# Floyd-V2-Sch.net
KiCad netlist of a schematic drawn in Altium Designer
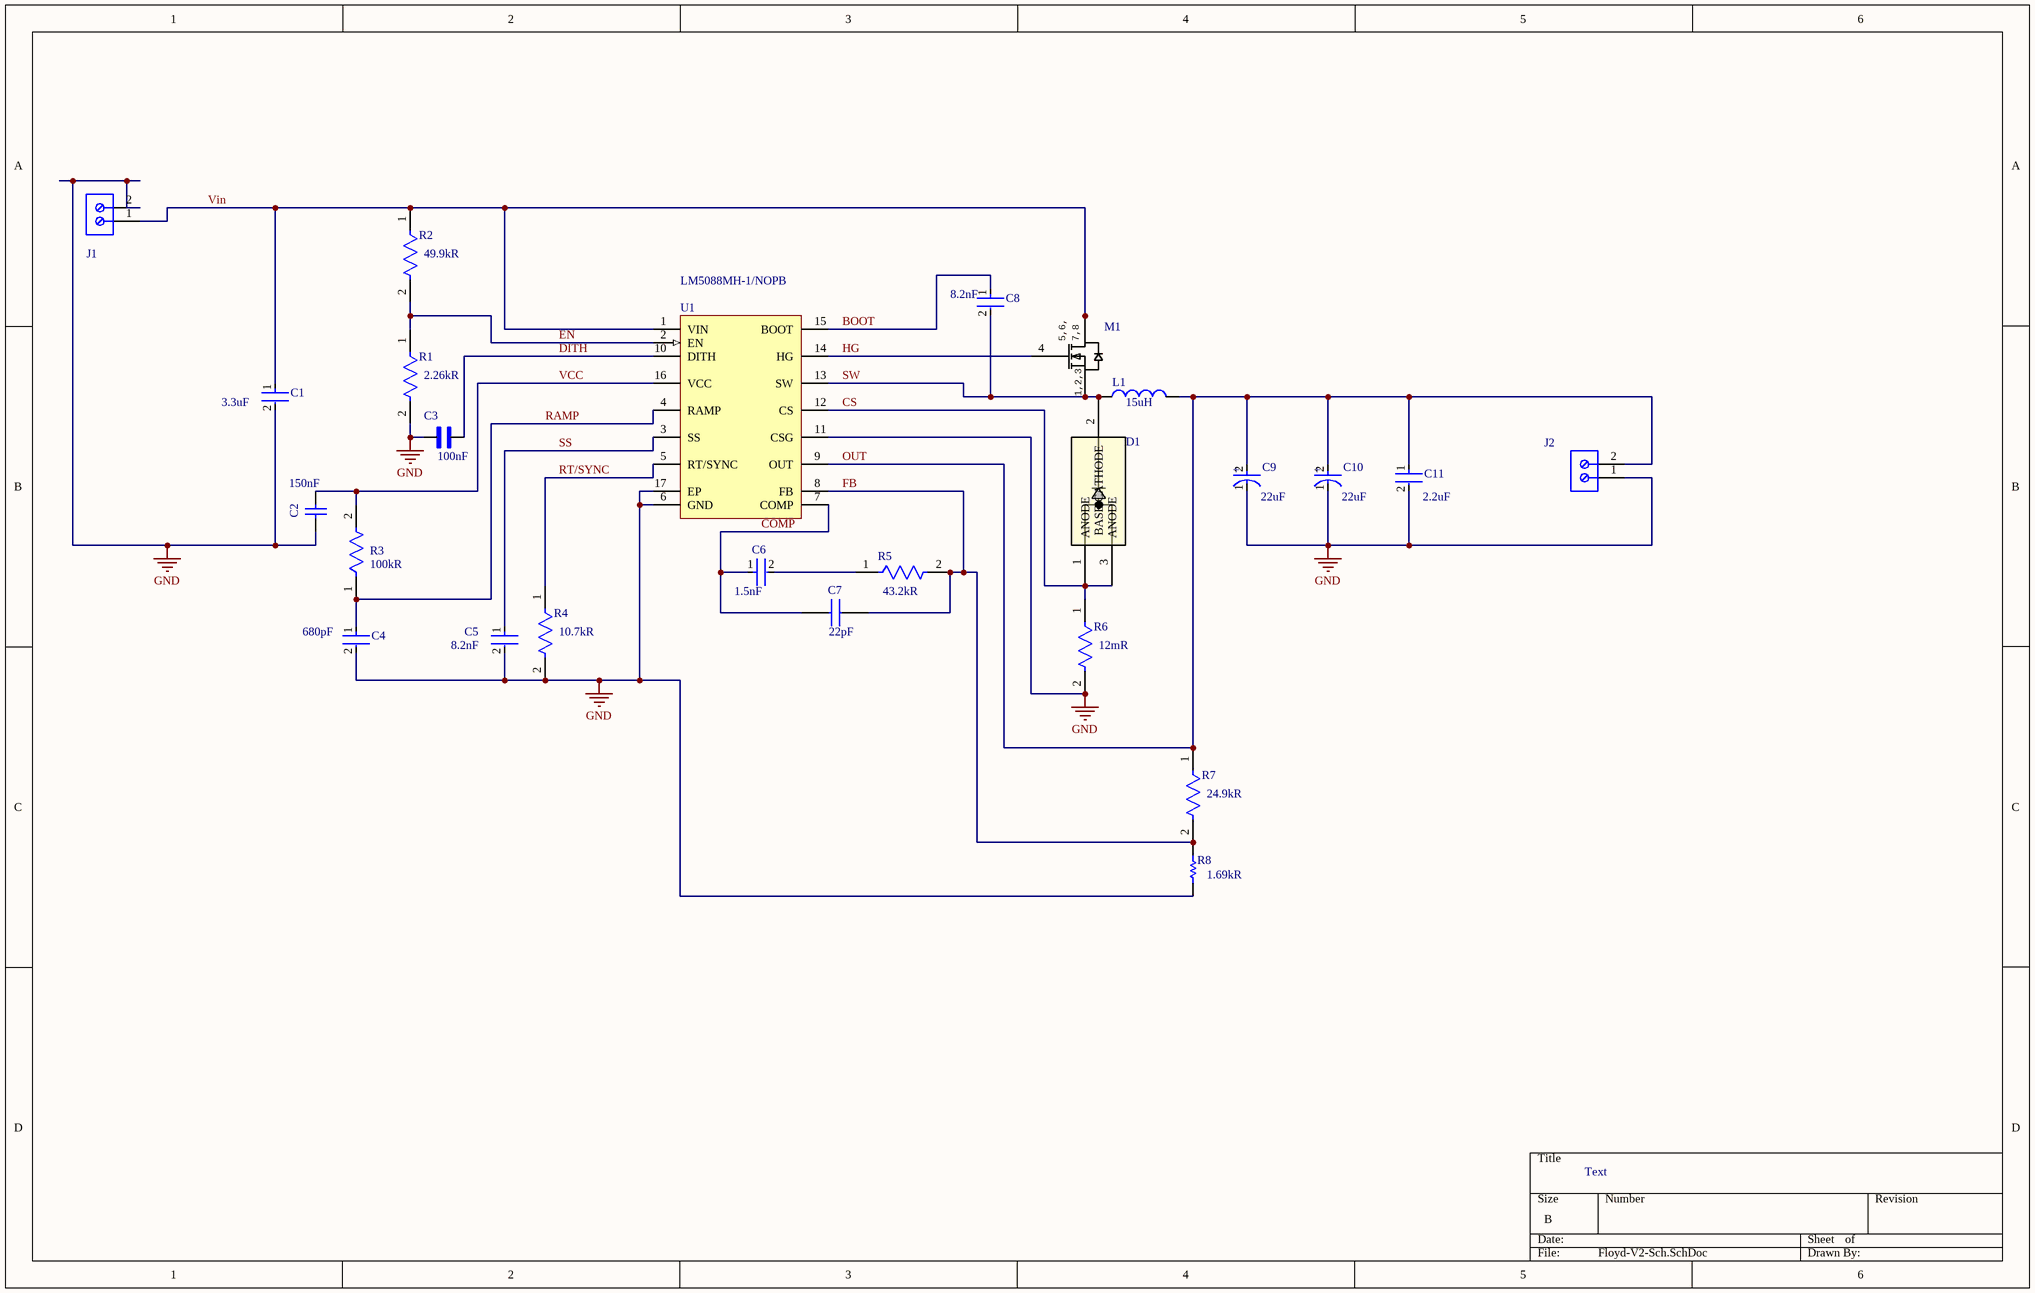
[diagram p0: Floyd-V2-Sch.SchDoc]

(export (version "E")
  (design (tool "Eeschema 10.0.6"))
  (components
    (comp (ref "C1")
      (value "C3225X7S2A335K200AB")
      (footprint "FP-C3225-200-0_4-IPC_A")
      (description "Multilayer Ceramic Capacitors 3.3uF ±10% 100V X7S SMD 1210")
      (fields (field (name "TOLERANCE") "10%") (field (name "CAPACITANCE") "3.3uF"))
      (libsource (lib "Altium Content Vault") (part "b4654b650e69147ec39a6b967a45e02"))
    )
    (comp (ref "C2")
      (value "08053C154KAT2A")
      (footprint "CAPC2013X140X50LL20T25")
      (fields (field (name "MANUFACTURER") "AVX Interconnect / Elco") (field (name "PARAMETER 1") "150nF"))
      (libsource (lib "Altium Content Vault") (part "CAP"))
    )
    (comp (ref "C3")
      (value "100nF")
      (footprint "CAPC2012X94N")
      (description "0.1 ÂµF Â±5% 25V Ceramic Capacitor X7R 0805 (2012 Metric)")
      (fields (field (name "MF") "AVX") (field (name "MP") "08053C104JAZ2A"))
      (libsource (lib "LoganIntegratedLibrary") (part "08053C104JAZ2A"))
    )
    (comp (ref "C4")
      (value "CC0805JRNPO9BN681")
      (footprint "FP-CC0805-0_1-0_7-MFG")
      (description "CAP CER 680PF 50V C0G/NPO 0805")
      (fields
        (field (name "TOLERANCE") "5%")
        (field (name "CAPACITANCE") "680pF")
        (field (name "VOLTAGE") "50V")
      )
      (libsource (lib "Altium Content Vault") (part "b4654b650e69147ec39a6b967a45e02"))
    )
    (comp (ref "C5")
      (value "CGA4C2C0G1H822J060AA")
      (footprint "FP-CGA4J-IPC_A")
      (description "Cap Ceramic 8.2nF 50V C0G 5% Pad SMD 0805 +125°C Automotive T/R")
      (fields (field (name "CAPACITANCE") "8.2nF") (field (name "TOLERANCE") "5%"))
      (libsource (lib "Altium Content Vault") (part "b4654b650e69147ec39a6b967a45e02"))
    )
    (comp (ref "C6")
      (value "C0603C152K5RACTU")
      (footprint "FP-C0603C-CF-MFG")
      (description "CAP CER 1500PF 50V X7R 0603")
      (fields
        (field (name "CAPACITANCE") "1.5nF")
        (field (name "TOLERANCE") "0.1")
        (field (name "OCTOPART") "https://octopart.com/c0603c152k5ractu-kemet-137039")
      )
      (libsource (lib "Altium Content Vault") (part "b4654b650e69147ec39a6b967a45e02"))
    )
    (comp (ref "C7")
      (value "CL10C220JB8NNNC")
      (footprint "CAPC1608X90N")
      (fields (field (name "MOUSER PART NUMBER") "187-CL10C220JB8NNNC") (field (name "PARAMETER 1") "22pF"))
      (libsource (lib "LoganIntegratedLibrary") (part "CL10C220JB8NNNC"))
    )
    (comp (ref "C8")
      (value "CGA4C2C0G1H822J060AA")
      (footprint "FP-CGA4J-IPC_A")
      (description "Cap Ceramic 8.2nF 50V C0G 5% Pad SMD 0805 +125°C Automotive T/R")
      (fields (field (name "CAPACITANCE") "8.2nF") (field (name "TOLERANCE") "5%"))
      (libsource (lib "Altium Content Vault") (part "b4654b650e69147ec39a6b967a45e02"))
    )
    (comp (ref "C9")
      (value "35SVPF22M")
      (footprint "FP-OS-CON-SMT-C6-MFG")
      (description "Conductive Polymer Aluminum Solid Capacitors (OS-CON) 22uF ±20% 35V")
      (fields
        (field (name "CAPACITANCE") "22uF")
        (field (name "TOLERANCE") "20%")
        (field (name "VOLTAGE") "35V")
      )
      (libsource (lib "Altium Content Vault") (part "a00bbbee19879c290e62620ae7e47b1"))
    )
    (comp (ref "C10")
      (value "35SVPF22M")
      (footprint "FP-OS-CON-SMT-C6-MFG")
      (description "Conductive Polymer Aluminum Solid Capacitors (OS-CON) 22uF ±20% 35V")
      (fields
        (field (name "CAPACITANCE") "22uF")
        (field (name "TOLERANCE") "20%")
        (field (name "VOLTAGE") "35V")
      )
      (libsource (lib "Altium Content Vault") (part "a00bbbee19879c290e62620ae7e47b1"))
    )
    (comp (ref "C11")
      (value "C2012X5R1E225K125AC")
      (footprint "FP-C2012-125-0_2-IPC_A")
      (description "Multilayer Ceramic Capacitors 2.2μF ±10% 25V X5R SMD 0805")
      (fields (field (name "TOLERANCE") "10%") (field (name "CAPACITANCE") "2.2uF"))
      (libsource (lib "Altium Content Vault") (part "b4654b650e69147ec39a6b967a45e02"))
    )
    (comp (ref "D1")
      (value "SBRD10200TR")
      (footprint "DPAK_SBRD10200_6P6X6P1_SDS")
      (description "Description")
      (fields (field (name "COPYRIGHT") "Copyright (C) 2025 Ultra Librarian. All rights reserved."))
      (libsource (lib "LoganIntegratedLibrary") (part "SBRD10200TR"))
    )
    (comp (ref "J1")
      (value "691137710002")
      (footprint "691137710002")
      (description "WR-TBL Series 1377 Horizontal Entry, THT, pitch 5mm, 02p")
      (fields (field (name "MANUFACTURER") "Wurth Elektronik"))
      (libsource (lib "LoganIntegratedLibrary") (part "691137710002"))
    )
    (comp (ref "J2")
      (value "691137710002")
      (footprint "691137710002")
      (description "WR-TBL Series 1377 Horizontal Entry, THT, pitch 5mm, 02p")
      (fields (field (name "MANUFACTURER") "Wurth Elektronik"))
      (libsource (lib "LoganIntegratedLibrary") (part "691137710002"))
    )
    (comp (ref "L1")
      (value "15uH")
      (footprint "IND_MSS1210-153MEB")
      (description "Power inductor, shielded, 10/20% tol, SMT, RoHS")
      (fields (field (name "MF") "Coilcraft") (field (name "MP") "MSS1210-153MEB"))
      (libsource (lib "LoganIntegratedLibrary") (part "MSS1210-153MEB"))
    )
    (comp (ref "M1")
      (value "CSD18543Q3A")
      (footprint "DNH0008A_NV")
      (description "60-V, N channel NexFETâ„¢ power MOSFET, single SON 3 mm x 3 mm, 9.9 mOhm 8-VSONP -55 to 150")
      (fields (field (name "COPYRIGHT") "Copyright (C) 2026 Ultra Librarian. All rights reserved."))
      (libsource (lib "LoganIntegratedLibrary") (part "CSD18543Q3A"))
    )
    (comp (ref "R1")
      (value "CRCW08052K26FKEA")
      (footprint "FP-CRCW0805-e3-IPC_C")
      (description "RES Thick Film, 2.26kΩ, 1%, 0.125W, 100ppm/°C, 0805")
      (fields (field (name "TOLERANCE") "1%") (field (name "RESISTANCE") "2.26kR"))
      (libsource (lib "Altium Content Vault") (part "1029c3af85768c4190bb7ad29bc67b5"))
    )
    (comp (ref "R2")
      (value "CRCW080549K9FKEA")
      (footprint "FP-CRCW0805-e3-IPC_C")
      (description "RES Thick Film, 49.9kΩ, 1%, 0.125W, 100ppm/°C, 0805")
      (fields (field (name "RESISTANCE") "49.9kR") (field (name "TOLERANCE") "1%"))
      (libsource (lib "Altium Content Vault") (part "1029c3af85768c4190bb7ad29bc67b5"))
    )
    (comp (ref "R3")
      (value "CRCW0805100KFKEA")
      (footprint "FP-CRCW0805-e3-MFG")
      (description "RES Thick Film, 100kΩ, 1%, 0.125W, 100ppm/°C, 0805")
      (fields (field (name "RESISTANCE") "100kR") (field (name "TOLERANCE") "1%"))
      (libsource (lib "Altium Content Vault") (part "1029c3af85768c4190bb7ad29bc67b5"))
    )
    (comp (ref "R4")
      (value "CRCW080510K7FKEA")
      (footprint "FP-CRCW0805-e3-IPC_C")
      (description "RES Thick Film, 10.7kΩ, 1%, 0.125W, 100ppm/°C, 0805")
      (fields (field (name "TOLERANCE") "1%") (field (name "RESISTANCE") "10.7kR"))
      (libsource (lib "Altium Content Vault") (part "1029c3af85768c4190bb7ad29bc67b5"))
    )
    (comp (ref "R5")
      (value "CRCW060343K2FKEA")
      (footprint "FP-CRCW0603-e3-MFG")
      (description "RES Thick Film, 43.2kΩ, 1%, 0.1W, 100ppm/°C, 0603")
      (fields (field (name "TOLERANCE") "1%") (field (name "RESISTANCE") "43.2kR"))
      (libsource (lib "Altium Content Vault") (part "1029c3af85768c4190bb7ad29bc67b5"))
    )
    (comp (ref "R6")
      (value "CSR1206FK12L0")
      (footprint "FP-CSR1206-IPC_B")
      (description "General Purpose Thick Film Chip Resistor, 1206, 12mΩ, 1%, 0.5W")
      (fields (field (name "TOLERANCE") "1%") (field (name "RESISTANCE") "12mR"))
      (libsource (lib "Altium Content Vault") (part "1029c3af85768c4190bb7ad29bc67b5"))
    )
    (comp (ref "R7")
      (value "CRCW040224K9FKED")
      (footprint "FP-CRCW0402-e3-IPC_C")
      (description "RES Thick Film, 24.9kΩ, 1%, 0.063W, 100ppm/°C, 0402")
      (fields (field (name "RESISTANCE") "24.9kR") (field (name "TOLERANCE") "1%"))
      (libsource (lib "Altium Content Vault") (part "1029c3af85768c4190bb7ad29bc67b5"))
    )
    (comp (ref "R8")
      (value "CRCW06031K69FKEA")
      (footprint "RESC1609X50X30ML10T20")
      (fields (field (name "MANUFACTURER") "Vishay Dale") (field (name "PARAMETER 1") "1.69kR"))
      (libsource (lib "Altium Content Vault") (part "RES"))
    )
    (comp (ref "U1")
      (value "LM5088MH-1/NOPB")
      (footprint "MXA16A")
      (description "Wide Input Range Non-Synchronous Buck Controller, 16-pin TSSOP-EP, Pb-Free")
      (fields (field (name "MANUFACTURER") "Texas Instruments"))
      (libsource (lib "LoganIntegratedLibrary") (part "PM-SWREG-LM5088-1-17"))
    )
  )
  (nets
    (net (code "1") (name "/BOOT") (class "Default")
      (node (ref "C8") (pin "1") (pinfunction "1_1") (pintype "passive"))
      (node (ref "U1") (pin "15") (pinfunction "BOOT_15") (pintype "passive"))
    )
    (net (code "2") (name "/COMP") (class "Default")
      (node (ref "C6") (pin "1") (pinfunction "1_1") (pintype "passive"))
      (node (ref "C7") (pin "1") (pinfunction "1_1") (pintype "passive"))
      (node (ref "U1") (pin "7") (pinfunction "COMP_7") (pintype "power_in"))
    )
    (net (code "3") (name "/CS") (class "Default")
      (node (ref "D1") (pin "1") (pinfunction "ANODE_1") (pintype "passive"))
      (node (ref "D1") (pin "3") (pinfunction "ANODE_3") (pintype "passive"))
      (node (ref "R6") (pin "1") (pinfunction "1_1") (pintype "passive"))
      (node (ref "U1") (pin "12") (pinfunction "CS_12") (pintype "passive"))
    )
    (net (code "4") (name "/DITH") (class "Default")
      (node (ref "C3") (pin "2") (pinfunction "2_2") (pintype "passive"))
      (node (ref "U1") (pin "10") (pinfunction "DITH_10") (pintype "passive"))
    )
    (net (code "5") (name "/EN") (class "Default")
      (node (ref "R1") (pin "1") (pinfunction "1_1") (pintype "passive"))
      (node (ref "R2") (pin "2") (pinfunction "2_2") (pintype "passive"))
      (node (ref "U1") (pin "2") (pinfunction "EN_2") (pintype "input"))
    )
    (net (code "6") (name "/FB") (class "Default")
      (node (ref "C7") (pin "2") (pinfunction "2_2") (pintype "passive"))
      (node (ref "R5") (pin "2") (pinfunction "2_2") (pintype "passive"))
      (node (ref "R7") (pin "2") (pinfunction "2_2") (pintype "passive"))
      (node (ref "R8") (pin "2") (pinfunction "2_2") (pintype "passive"))
      (node (ref "U1") (pin "8") (pinfunction "FB_8") (pintype "power_in"))
    )
    (net (code "7") (name "/HG") (class "Default")
      (node (ref "M1") (pin "4") (pinfunction "G_4") (pintype "passive"))
      (node (ref "U1") (pin "14") (pinfunction "HG_14") (pintype "power_in"))
    )
    (net (code "8") (name "/OUT") (class "Default")
      (node (ref "C10") (pin "2") (pinfunction "A_2") (pintype "passive"))
      (node (ref "C11") (pin "1") (pinfunction "1_1") (pintype "passive"))
      (node (ref "C9") (pin "2") (pinfunction "A_2") (pintype "passive"))
      (node (ref "J2") (pin "2") (pinfunction "2_2") (pintype "passive"))
      (node (ref "L1") (pin "2") (pinfunction "2_2") (pintype "passive"))
      (node (ref "R7") (pin "1") (pinfunction "1_1") (pintype "passive"))
      (node (ref "U1") (pin "9") (pinfunction "OUT_9") (pintype "passive"))
    )
    (net (code "9") (name "/RAMP") (class "Default")
      (node (ref "C4") (pin "1") (pinfunction "1_1") (pintype "passive"))
      (node (ref "R3") (pin "1") (pinfunction "1_1") (pintype "passive"))
      (node (ref "U1") (pin "4") (pinfunction "RAMP_4") (pintype "passive"))
    )
    (net (code "10") (name "/RT{slash}SYNC") (class "Default")
      (node (ref "R4") (pin "1") (pinfunction "1_1") (pintype "passive"))
      (node (ref "U1") (pin "5") (pinfunction "RT/SYNC_5") (pintype "passive"))
    )
    (net (code "11") (name "/SS") (class "Default")
      (node (ref "C5") (pin "1") (pinfunction "1_1") (pintype "passive"))
      (node (ref "U1") (pin "3") (pinfunction "SS_3") (pintype "passive"))
    )
    (net (code "12") (name "/SW") (class "Default")
      (node (ref "C8") (pin "2") (pinfunction "2_2") (pintype "passive"))
      (node (ref "D1") (pin "2") (pinfunction "BASE_CATHODE_2") (pintype "passive"))
      (node (ref "L1") (pin "1") (pinfunction "1_1") (pintype "passive"))
      (node (ref "M1") (pin "1") (pinfunction "S_1") (pintype "passive"))
      (node (ref "M1") (pin "2") (pinfunction "S_2") (pintype "passive"))
      (node (ref "M1") (pin "3") (pinfunction "S_3") (pintype "passive"))
      (node (ref "U1") (pin "13") (pinfunction "SW_13") (pintype "power_in"))
    )
    (net (code "13") (name "/VCC") (class "Default")
      (node (ref "C2") (pin "2") (pinfunction "2_2") (pintype "passive"))
      (node (ref "R3") (pin "2") (pinfunction "2_2") (pintype "passive"))
      (node (ref "U1") (pin "16") (pinfunction "VCC_16") (pintype "power_in"))
    )
    (net (code "14") (name "/Vin") (class "Default")
      (node (ref "C1") (pin "1") (pinfunction "1_1") (pintype "passive"))
      (node (ref "J1") (pin "1") (pinfunction "1_1") (pintype "passive"))
      (node (ref "M1") (pin "5") (pinfunction "D_5") (pintype "passive"))
      (node (ref "M1") (pin "6") (pinfunction "D_6") (pintype "passive"))
      (node (ref "M1") (pin "7") (pinfunction "D_7") (pintype "passive"))
      (node (ref "M1") (pin "8") (pinfunction "D_8") (pintype "passive"))
      (node (ref "M1") (pin "9") (pinfunction "D_9") (pintype "passive"))
      (node (ref "R2") (pin "1") (pinfunction "1_1") (pintype "passive"))
      (node (ref "U1") (pin "1") (pinfunction "VIN_1") (pintype "passive"))
    )
    (net (code "15") (name "GND") (class "Default")
      (node (ref "C1") (pin "2") (pinfunction "2_2") (pintype "passive"))
      (node (ref "C10") (pin "1") (pinfunction "C_1") (pintype "passive"))
      (node (ref "C11") (pin "2") (pinfunction "2_2") (pintype "passive"))
      (node (ref "C2") (pin "1") (pinfunction "1_1") (pintype "passive"))
      (node (ref "C3") (pin "1") (pinfunction "1_1") (pintype "passive"))
      (node (ref "C4") (pin "2") (pinfunction "2_2") (pintype "passive"))
      (node (ref "C5") (pin "2") (pinfunction "2_2") (pintype "passive"))
      (node (ref "C9") (pin "1") (pinfunction "C_1") (pintype "passive"))
      (node (ref "J1") (pin "2") (pinfunction "2_2") (pintype "passive"))
      (node (ref "J2") (pin "1") (pinfunction "1_1") (pintype "passive"))
      (node (ref "R1") (pin "2") (pinfunction "2_2") (pintype "passive"))
      (node (ref "R4") (pin "2") (pinfunction "2_2") (pintype "passive"))
      (node (ref "R6") (pin "2") (pinfunction "2_2") (pintype "passive"))
      (node (ref "R8") (pin "1") (pinfunction "1_1") (pintype "passive"))
      (node (ref "U1") (pin "11") (pinfunction "CSG_11") (pintype "power_in"))
      (node (ref "U1") (pin "17") (pinfunction "EP_17") (pintype "passive"))
      (node (ref "U1") (pin "6") (pinfunction "GND_6") (pintype "power_in"))
    )
    (net (code "16") (name "Net-(C6-Pad2)") (class "Default")
      (node (ref "C6") (pin "2") (pinfunction "2_2") (pintype "passive"))
      (node (ref "R5") (pin "1") (pinfunction "1_1") (pintype "passive"))
    )
  )
)
